# MicroMultimeter_KEY_Sch.net
KiCad netlist of a schematic drawn in Altium Designer
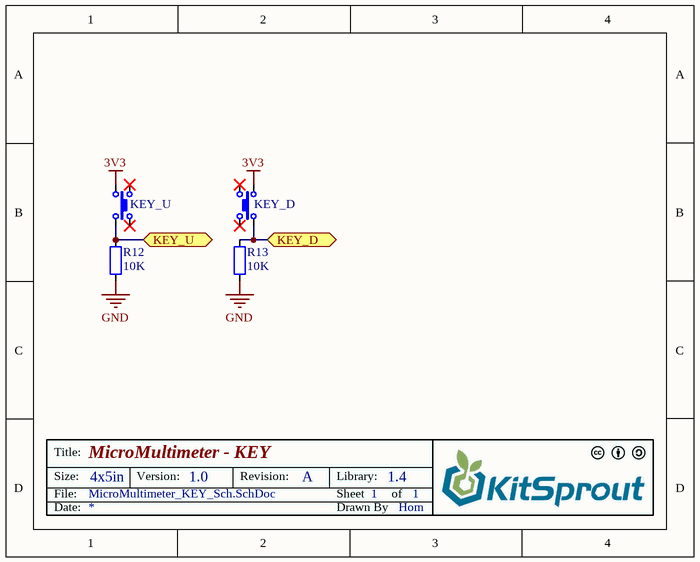
[diagram p0: MicroMultimeter_KEY_Sch.SchDoc]

(export (version "E")
  (design (tool "Eeschema 10.0.6"))
  (components
    (comp (ref "KEY_D")
      (value "ButtonTACT")
      (footprint "ButtonTACT_3.5*3.55_90")
      (description "Button")
      (libsource (lib "SCH_Switch") (part "ButtonTACT"))
    )
    (comp (ref "KEY_U")
      (value "ButtonTACT")
      (footprint "ButtonTACT_3.5*3.55_90")
      (description "Button")
      (libsource (lib "SCH_Switch") (part "ButtonTACT"))
    )
    (comp (ref "R12")
      (value "10K")
      (footprint "RES_0603")
      (description "Resistor")
      (fields (field (name "Comment") "Res_0603"))
      (libsource (lib "SCH_Passive") (part "Res_0603"))
    )
    (comp (ref "R13")
      (value "10K")
      (footprint "RES_0603")
      (description "Resistor")
      (fields (field (name "Comment") "Res_0603"))
      (libsource (lib "SCH_Passive") (part "Res_0603"))
    )
  )
  (nets
    (net (code "1") (name "/KEY_D") (class "Default")
      (node (ref "KEY_D") (pin "3") (pinfunction "3_3") (pintype "passive"))
      (node (ref "R13") (pin "2") (pinfunction "2_2") (pintype "passive"))
    )
    (net (code "2") (name "/KEY_U") (class "Default")
      (node (ref "KEY_U") (pin "4") (pinfunction "4_4") (pintype "passive"))
      (node (ref "R12") (pin "2") (pinfunction "2_2") (pintype "passive"))
    )
    (net (code "3") (name "3V3") (class "Default")
      (node (ref "KEY_D") (pin "4") (pinfunction "4_4") (pintype "passive"))
      (node (ref "KEY_U") (pin "3") (pinfunction "3_3") (pintype "passive"))
    )
    (net (code "4") (name "GND") (class "Default")
      (node (ref "R12") (pin "1") (pinfunction "1_1") (pintype "passive"))
      (node (ref "R13") (pin "1") (pinfunction "1_1") (pintype "passive"))
    )
    (net (code "5") (name "unconnected-(KEY_D-Pad1)") (class "Default")
      (node (ref "KEY_D") (pin "1") (pinfunction "1_1") (pintype "passive+no_connect"))
    )
    (net (code "6") (name "unconnected-(KEY_D-Pad2)") (class "Default")
      (node (ref "KEY_D") (pin "2") (pinfunction "2_2") (pintype "passive+no_connect"))
    )
    (net (code "7") (name "unconnected-(KEY_U-Pad1)") (class "Default")
      (node (ref "KEY_U") (pin "1") (pinfunction "1_1") (pintype "passive+no_connect"))
    )
    (net (code "8") (name "unconnected-(KEY_U-Pad2)") (class "Default")
      (node (ref "KEY_U") (pin "2") (pinfunction "2_2") (pintype "passive+no_connect"))
    )
  )
)
